# PCB_Terminal_Block_Connector.net
KiCad netlist of a schematic drawn in EAGLE
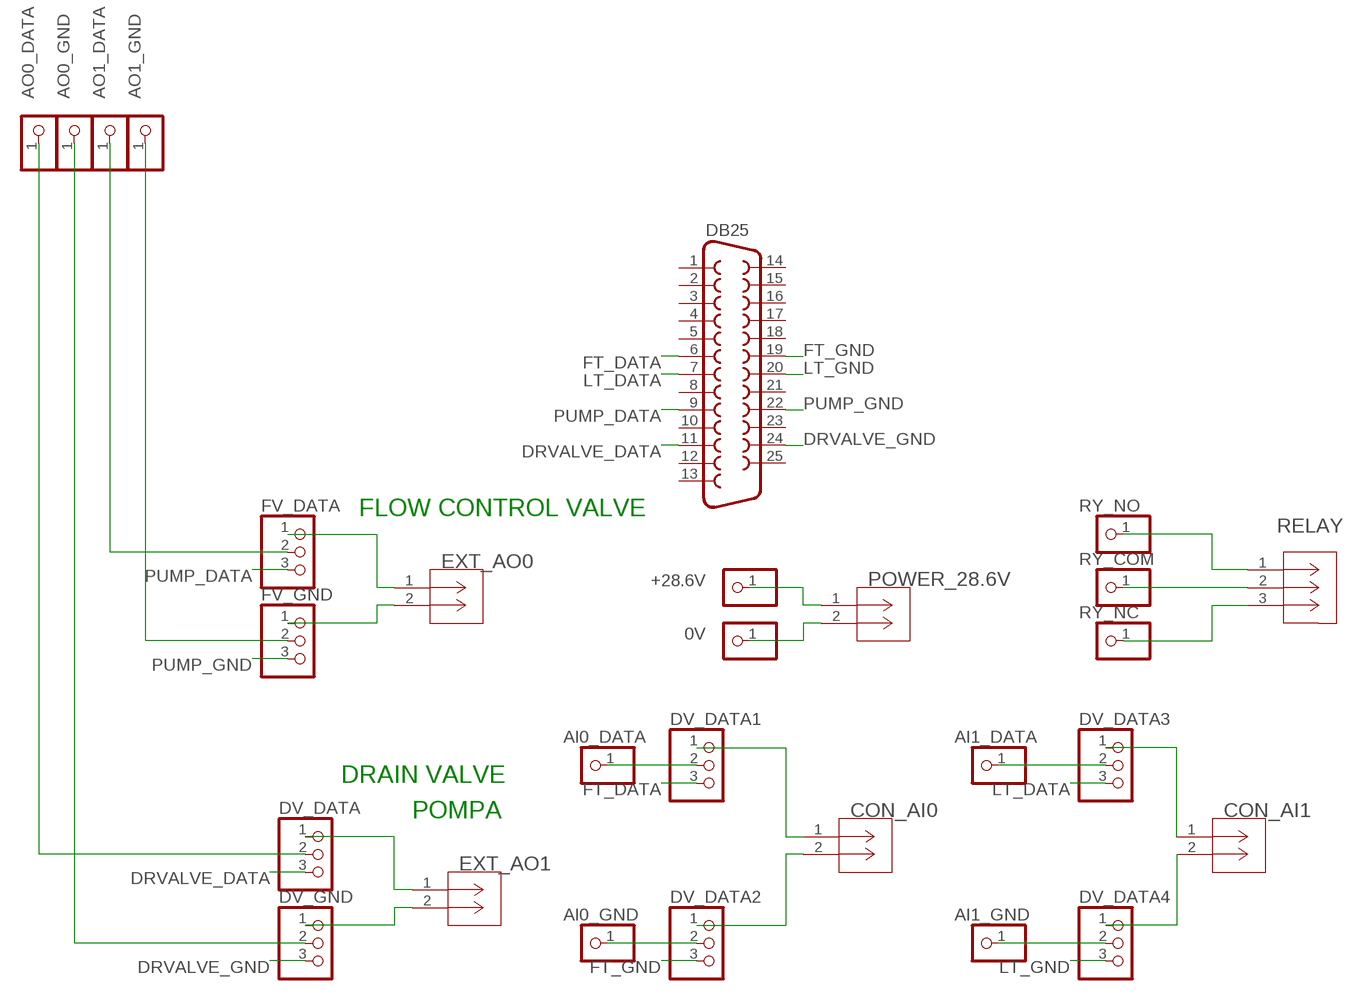
[diagram p0: schematic, sheet 1]

(export (version "E")
  (design (tool "Eeschema 10.0.6"))
  (components
    (comp (ref "+28.6V")
      (value "PINHD-1X1")
      (footprint "eagle-import:1X01")
      (libsource (lib "eagle-import") (part "PINHD-1X1"))
    )
    (comp (ref "0V")
      (value "PINHD-1X1")
      (footprint "eagle-import:1X01")
      (libsource (lib "eagle-import") (part "PINHD-1X1"))
    )
    (comp (ref "AI0_DATA")
      (value "PINHD-1X1")
      (footprint "eagle-import:1X01")
      (libsource (lib "eagle-import") (part "PINHD-1X1"))
    )
    (comp (ref "AI0_GND")
      (value "PINHD-1X1")
      (footprint "eagle-import:1X01")
      (libsource (lib "eagle-import") (part "PINHD-1X1"))
    )
    (comp (ref "AI1_DATA")
      (value "PINHD-1X1")
      (footprint "eagle-import:1X01")
      (libsource (lib "eagle-import") (part "PINHD-1X1"))
    )
    (comp (ref "AI1_GND")
      (value "PINHD-1X1")
      (footprint "eagle-import:1X01")
      (libsource (lib "eagle-import") (part "PINHD-1X1"))
    )
    (comp (ref "AO0_DATA")
      (value "PINHD-1X1")
      (footprint "eagle-import:1X01")
      (libsource (lib "eagle-import") (part "PINHD-1X1"))
    )
    (comp (ref "AO0_GND")
      (value "PINHD-1X1")
      (footprint "eagle-import:1X01")
      (libsource (lib "eagle-import") (part "PINHD-1X1"))
    )
    (comp (ref "AO1_DATA")
      (value "PINHD-1X1")
      (footprint "eagle-import:1X01")
      (libsource (lib "eagle-import") (part "PINHD-1X1"))
    )
    (comp (ref "AO1_GND")
      (value "PINHD-1X1")
      (footprint "eagle-import:1X01")
      (libsource (lib "eagle-import") (part "PINHD-1X1"))
    )
    (comp (ref "CON_AI0")
      (value "KF8500-8.5-2P")
      (footprint "eagle-import:CONN_KF8500-8.5-2P_CKE")
      (fields (field (name "COPYRIGHT") "Copyright (C) 2023 Ultra Librarian. All rights reserved."))
      (libsource (lib "eagle-import") (part "KF8500-8.5-2P"))
    )
    (comp (ref "CON_AI1")
      (value "KF8500-8.5-2P")
      (footprint "eagle-import:CONN_KF8500-8.5-2P_CKE")
      (fields (field (name "COPYRIGHT") "Copyright (C) 2023 Ultra Librarian. All rights reserved."))
      (libsource (lib "eagle-import") (part "KF8500-8.5-2P"))
    )
    (comp (ref "DB25")
      (value "F25H")
      (footprint "eagle-import:F25H")
      (libsource (lib "eagle-import") (part "F25H"))
    )
    (comp (ref "DV_DATA")
      (value "PINHD-1X3")
      (footprint "eagle-import:1X03")
      (libsource (lib "eagle-import") (part "PINHD-1X3"))
    )
    (comp (ref "DV_DATA1")
      (value "PINHD-1X3")
      (footprint "eagle-import:1X03")
      (libsource (lib "eagle-import") (part "PINHD-1X3"))
    )
    (comp (ref "DV_DATA2")
      (value "PINHD-1X3")
      (footprint "eagle-import:1X03")
      (libsource (lib "eagle-import") (part "PINHD-1X3"))
    )
    (comp (ref "DV_DATA3")
      (value "PINHD-1X3")
      (footprint "eagle-import:1X03")
      (libsource (lib "eagle-import") (part "PINHD-1X3"))
    )
    (comp (ref "DV_DATA4")
      (value "PINHD-1X3")
      (footprint "eagle-import:1X03")
      (libsource (lib "eagle-import") (part "PINHD-1X3"))
    )
    (comp (ref "DV_GND")
      (value "PINHD-1X3")
      (footprint "eagle-import:1X03")
      (libsource (lib "eagle-import") (part "PINHD-1X3"))
    )
    (comp (ref "EXT_AO0")
      (value "KF8500-8.5-2P")
      (footprint "eagle-import:CONN_KF8500-8.5-2P_CKE")
      (fields (field (name "COPYRIGHT") "Copyright (C) 2023 Ultra Librarian. All rights reserved."))
      (libsource (lib "eagle-import") (part "KF8500-8.5-2P"))
    )
    (comp (ref "EXT_AO1")
      (value "KF8500-8.5-2P")
      (footprint "eagle-import:CONN_KF8500-8.5-2P_CKE")
      (fields (field (name "COPYRIGHT") "Copyright (C) 2023 Ultra Librarian. All rights reserved."))
      (libsource (lib "eagle-import") (part "KF8500-8.5-2P"))
    )
    (comp (ref "FV_DATA")
      (value "PINHD-1X3")
      (footprint "eagle-import:1X03")
      (libsource (lib "eagle-import") (part "PINHD-1X3"))
    )
    (comp (ref "FV_GND")
      (value "PINHD-1X3")
      (footprint "eagle-import:1X03")
      (libsource (lib "eagle-import") (part "PINHD-1X3"))
    )
    (comp (ref "POWER_28.6V")
      (value "KF8500-8.5-2P")
      (footprint "eagle-import:CONN_KF8500-8.5-2P_CKE")
      (fields (field (name "COPYRIGHT") "Copyright (C) 2023 Ultra Librarian. All rights reserved."))
      (libsource (lib "eagle-import") (part "KF8500-8.5-2P"))
    )
    (comp (ref "RELAY")
      (value "KF8500-8.5-4P")
      (footprint "eagle-import:CONN4_KF8500_1X4_1398X472_CKE")
      (fields (field (name "COPYRIGHT") "Copyright (C) 2023 Ultra Librarian. All rights reserved."))
      (libsource (lib "eagle-import") (part "KF8500-8.5-4P"))
    )
    (comp (ref "RY_COM")
      (value "PINHD-1X1")
      (footprint "eagle-import:1X01")
      (libsource (lib "eagle-import") (part "PINHD-1X1"))
    )
    (comp (ref "RY_NC")
      (value "PINHD-1X1")
      (footprint "eagle-import:1X01")
      (libsource (lib "eagle-import") (part "PINHD-1X1"))
    )
    (comp (ref "RY_NO")
      (value "PINHD-1X1")
      (footprint "eagle-import:1X01")
      (libsource (lib "eagle-import") (part "PINHD-1X1"))
    )
  )
  (nets
    (net (code "1") (name "/DRVALVE_DATA") (class "Default")
      (node (ref "DB25") (pin "11") (pinfunction "11_11") (pintype "passive"))
      (node (ref "DV_DATA") (pin "3") (pinfunction "3_3") (pintype "passive"))
    )
    (net (code "2") (name "/DRVALVE_GND") (class "Default")
      (node (ref "DB25") (pin "24") (pinfunction "24_24") (pintype "passive"))
      (node (ref "DV_GND") (pin "3") (pinfunction "3_3") (pintype "passive"))
    )
    (net (code "3") (name "/FT_DATA") (class "Default")
      (node (ref "DB25") (pin "6") (pinfunction "6_6") (pintype "passive"))
      (node (ref "DV_DATA1") (pin "3") (pinfunction "3_3") (pintype "passive"))
    )
    (net (code "4") (name "/FT_GND") (class "Default")
      (node (ref "DB25") (pin "19") (pinfunction "19_19") (pintype "passive"))
      (node (ref "DV_DATA2") (pin "3") (pinfunction "3_3") (pintype "passive"))
    )
    (net (code "5") (name "/LT_DATA") (class "Default")
      (node (ref "DB25") (pin "7") (pinfunction "7_7") (pintype "passive"))
      (node (ref "DV_DATA3") (pin "3") (pinfunction "3_3") (pintype "passive"))
    )
    (net (code "6") (name "/LT_GND") (class "Default")
      (node (ref "DB25") (pin "20") (pinfunction "20_20") (pintype "passive"))
      (node (ref "DV_DATA4") (pin "3") (pinfunction "3_3") (pintype "passive"))
    )
    (net (code "7") (name "/PUMP_DATA") (class "Default")
      (node (ref "DB25") (pin "9") (pinfunction "9_9") (pintype "passive"))
      (node (ref "FV_DATA") (pin "3") (pinfunction "3_3") (pintype "passive"))
    )
    (net (code "8") (name "/PUMP_GND") (class "Default")
      (node (ref "DB25") (pin "22") (pinfunction "22_22") (pintype "passive"))
      (node (ref "FV_GND") (pin "3") (pinfunction "3_3") (pintype "passive"))
    )
    (net (code "9") (name "Net-(+28.6V-Pad1)") (class "Default")
      (node (ref "+28.6V") (pin "1") (pinfunction "1_1") (pintype "passive"))
      (node (ref "POWER_28.6V") (pin "1") (pinfunction "1_1") (pintype "passive"))
    )
    (net (code "10") (name "Net-(0V-Pad1)") (class "Default")
      (node (ref "0V") (pin "1") (pinfunction "1_1") (pintype "passive"))
      (node (ref "POWER_28.6V") (pin "2") (pinfunction "2_2") (pintype "passive"))
    )
    (net (code "11") (name "Net-(AI0_DATA-Pad1)") (class "Default")
      (node (ref "AI0_DATA") (pin "1") (pinfunction "1_1") (pintype "passive"))
      (node (ref "DV_DATA1") (pin "2") (pinfunction "2_2") (pintype "passive"))
    )
    (net (code "12") (name "Net-(AI0_GND-Pad1)") (class "Default")
      (node (ref "AI0_GND") (pin "1") (pinfunction "1_1") (pintype "passive"))
      (node (ref "DV_DATA2") (pin "2") (pinfunction "2_2") (pintype "passive"))
    )
    (net (code "13") (name "Net-(AI1_DATA-Pad1)") (class "Default")
      (node (ref "AI1_DATA") (pin "1") (pinfunction "1_1") (pintype "passive"))
      (node (ref "DV_DATA3") (pin "2") (pinfunction "2_2") (pintype "passive"))
    )
    (net (code "14") (name "Net-(AI1_GND-Pad1)") (class "Default")
      (node (ref "AI1_GND") (pin "1") (pinfunction "1_1") (pintype "passive"))
      (node (ref "DV_DATA4") (pin "2") (pinfunction "2_2") (pintype "passive"))
    )
    (net (code "15") (name "Net-(AO0_DATA-Pad1)") (class "Default")
      (node (ref "AO0_DATA") (pin "1") (pinfunction "1_1") (pintype "passive"))
      (node (ref "DV_DATA") (pin "2") (pinfunction "2_2") (pintype "passive"))
    )
    (net (code "16") (name "Net-(AO0_GND-Pad1)") (class "Default")
      (node (ref "AO0_GND") (pin "1") (pinfunction "1_1") (pintype "passive"))
      (node (ref "DV_GND") (pin "2") (pinfunction "2_2") (pintype "passive"))
    )
    (net (code "17") (name "Net-(AO1_DATA-Pad1)") (class "Default")
      (node (ref "AO1_DATA") (pin "1") (pinfunction "1_1") (pintype "passive"))
      (node (ref "FV_DATA") (pin "2") (pinfunction "2_2") (pintype "passive"))
    )
    (net (code "18") (name "Net-(AO1_GND-Pad1)") (class "Default")
      (node (ref "AO1_GND") (pin "1") (pinfunction "1_1") (pintype "passive"))
      (node (ref "FV_GND") (pin "2") (pinfunction "2_2") (pintype "passive"))
    )
    (net (code "19") (name "Net-(CON_AI0-Pad1)") (class "Default")
      (node (ref "CON_AI0") (pin "1") (pinfunction "1_1") (pintype "passive"))
      (node (ref "DV_DATA1") (pin "1") (pinfunction "1_1") (pintype "passive"))
    )
    (net (code "20") (name "Net-(CON_AI0-Pad2)") (class "Default")
      (node (ref "CON_AI0") (pin "2") (pinfunction "2_2") (pintype "passive"))
      (node (ref "DV_DATA2") (pin "1") (pinfunction "1_1") (pintype "passive"))
    )
    (net (code "21") (name "Net-(CON_AI1-Pad1)") (class "Default")
      (node (ref "CON_AI1") (pin "1") (pinfunction "1_1") (pintype "passive"))
      (node (ref "DV_DATA3") (pin "1") (pinfunction "1_1") (pintype "passive"))
    )
    (net (code "22") (name "Net-(CON_AI1-Pad2)") (class "Default")
      (node (ref "CON_AI1") (pin "2") (pinfunction "2_2") (pintype "passive"))
      (node (ref "DV_DATA4") (pin "1") (pinfunction "1_1") (pintype "passive"))
    )
    (net (code "23") (name "Net-(DV_DATA-Pad1)") (class "Default")
      (node (ref "DV_DATA") (pin "1") (pinfunction "1_1") (pintype "passive"))
      (node (ref "EXT_AO1") (pin "1") (pinfunction "1_1") (pintype "passive"))
    )
    (net (code "24") (name "Net-(DV_GND-Pad1)") (class "Default")
      (node (ref "DV_GND") (pin "1") (pinfunction "1_1") (pintype "passive"))
      (node (ref "EXT_AO1") (pin "2") (pinfunction "2_2") (pintype "passive"))
    )
    (net (code "25") (name "Net-(EXT_AO0-Pad1)") (class "Default")
      (node (ref "EXT_AO0") (pin "1") (pinfunction "1_1") (pintype "passive"))
      (node (ref "FV_DATA") (pin "1") (pinfunction "1_1") (pintype "passive"))
    )
    (net (code "26") (name "Net-(EXT_AO0-Pad2)") (class "Default")
      (node (ref "EXT_AO0") (pin "2") (pinfunction "2_2") (pintype "passive"))
      (node (ref "FV_GND") (pin "1") (pinfunction "1_1") (pintype "passive"))
    )
    (net (code "27") (name "Net-(RELAY-Pad1)") (class "Default")
      (node (ref "RELAY") (pin "1") (pinfunction "1_1") (pintype "passive"))
      (node (ref "RY_NO") (pin "1") (pinfunction "1_1") (pintype "passive"))
    )
    (net (code "28") (name "Net-(RELAY-Pad2)") (class "Default")
      (node (ref "RELAY") (pin "2") (pinfunction "2_2") (pintype "passive"))
      (node (ref "RY_COM") (pin "1") (pinfunction "1_1") (pintype "passive"))
    )
    (net (code "29") (name "Net-(RELAY-Pad3)") (class "Default")
      (node (ref "RELAY") (pin "3") (pinfunction "3_3") (pintype "passive"))
      (node (ref "RY_NC") (pin "1") (pinfunction "1_1") (pintype "passive"))
    )
    (net (code "30") (name "unconnected-(DB25-Pad1)") (class "Default")
      (node (ref "DB25") (pin "1") (pinfunction "1_1") (pintype "passive"))
    )
    (net (code "31") (name "unconnected-(DB25-Pad2)") (class "Default")
      (node (ref "DB25") (pin "2") (pinfunction "2_2") (pintype "passive"))
    )
    (net (code "32") (name "unconnected-(DB25-Pad3)") (class "Default")
      (node (ref "DB25") (pin "3") (pinfunction "3_3") (pintype "passive"))
    )
    (net (code "33") (name "unconnected-(DB25-Pad4)") (class "Default")
      (node (ref "DB25") (pin "4") (pinfunction "4_4") (pintype "passive"))
    )
    (net (code "34") (name "unconnected-(DB25-Pad5)") (class "Default")
      (node (ref "DB25") (pin "5") (pinfunction "5_5") (pintype "passive"))
    )
    (net (code "35") (name "unconnected-(DB25-Pad8)") (class "Default")
      (node (ref "DB25") (pin "8") (pinfunction "8_8") (pintype "passive"))
    )
    (net (code "36") (name "unconnected-(DB25-Pad10)") (class "Default")
      (node (ref "DB25") (pin "10") (pinfunction "10_10") (pintype "passive"))
    )
    (net (code "37") (name "unconnected-(DB25-Pad12)") (class "Default")
      (node (ref "DB25") (pin "12") (pinfunction "12_12") (pintype "passive"))
    )
    (net (code "38") (name "unconnected-(DB25-Pad13)") (class "Default")
      (node (ref "DB25") (pin "13") (pinfunction "13_13") (pintype "passive"))
    )
    (net (code "39") (name "unconnected-(DB25-Pad14)") (class "Default")
      (node (ref "DB25") (pin "14") (pinfunction "14_14") (pintype "passive"))
    )
    (net (code "40") (name "unconnected-(DB25-Pad15)") (class "Default")
      (node (ref "DB25") (pin "15") (pinfunction "15_15") (pintype "passive"))
    )
    (net (code "41") (name "unconnected-(DB25-Pad16)") (class "Default")
      (node (ref "DB25") (pin "16") (pinfunction "16_16") (pintype "passive"))
    )
    (net (code "42") (name "unconnected-(DB25-Pad17)") (class "Default")
      (node (ref "DB25") (pin "17") (pinfunction "17_17") (pintype "passive"))
    )
    (net (code "43") (name "unconnected-(DB25-Pad18)") (class "Default")
      (node (ref "DB25") (pin "18") (pinfunction "18_18") (pintype "passive"))
    )
    (net (code "44") (name "unconnected-(DB25-Pad21)") (class "Default")
      (node (ref "DB25") (pin "21") (pinfunction "21_21") (pintype "passive"))
    )
    (net (code "45") (name "unconnected-(DB25-Pad23)") (class "Default")
      (node (ref "DB25") (pin "23") (pinfunction "23_23") (pintype "passive"))
    )
    (net (code "46") (name "unconnected-(DB25-Pad25)") (class "Default")
      (node (ref "DB25") (pin "25") (pinfunction "25_25") (pintype "passive"))
    )
  )
)
